# Headphone-Amplifier-ClassAB-alt4.net
KiCad netlist of a schematic drawn in EAGLE
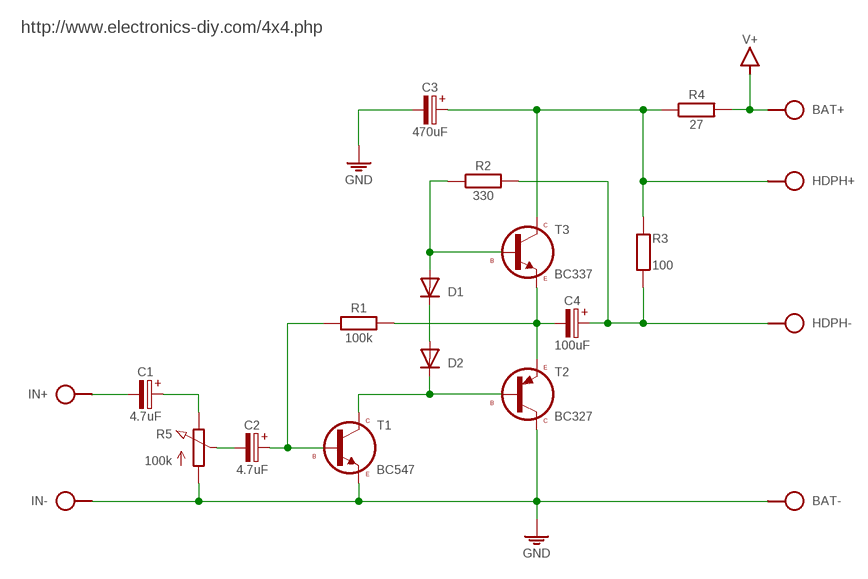
[diagram p0: schematic, sheet 1]

(export (version "E")
  (design (tool "Eeschema 10.0.6"))
  (components
    (comp (ref "BAT")
      (value "SPAD+-+-")
      (footprint "eagle-import:SPAD+-")
      (libsource (lib "eagle-import") (part "SPAD+-+-"))
    )
    (comp (ref "C1")
      (value "4.7uF")
      (footprint "eagle-import:E2,5-4")
      (libsource (lib "eagle-import") (part "CPOLE2,5-4"))
    )
    (comp (ref "C2")
      (value "4.7uF")
      (footprint "eagle-import:E2,5-4")
      (libsource (lib "eagle-import") (part "CPOLE2,5-4"))
    )
    (comp (ref "C3")
      (value "470uF")
      (footprint "eagle-import:E5-6")
      (libsource (lib "eagle-import") (part "CPOLE5-6"))
    )
    (comp (ref "C4")
      (value "100uF")
      (footprint "eagle-import:E5-4")
      (libsource (lib "eagle-import") (part "CPOLE5-4"))
    )
    (comp (ref "D1")
      (value "1N414834-5V")
      (footprint "eagle-import:DO34-5V")
      (libsource (lib "eagle-import") (part "1N414834-5V"))
    )
    (comp (ref "D2")
      (value "1N414834-5V")
      (footprint "eagle-import:DO34-5V")
      (libsource (lib "eagle-import") (part "1N414834-5V"))
    )
    (comp (ref "HDPH")
      (value "SPAD+--+")
      (footprint "eagle-import:SPAD-+")
      (libsource (lib "eagle-import") (part "SPAD+--+"))
    )
    (comp (ref "IN")
      (value "SPAD+--+")
      (footprint "eagle-import:SPAD-+")
      (libsource (lib "eagle-import") (part "SPAD+--+"))
    )
    (comp (ref "R1")
      (value "100k")
      (footprint "eagle-import:0202_7")
      (libsource (lib "eagle-import") (part "R-H0202/7"))
    )
    (comp (ref "R2")
      (value "330")
      (footprint "eagle-import:0202_7")
      (libsource (lib "eagle-import") (part "R-H0202/7"))
    )
    (comp (ref "R3")
      (value "100")
      (footprint "eagle-import:0202_7")
      (libsource (lib "eagle-import") (part "R0202/7"))
    )
    (comp (ref "R4")
      (value "27")
      (footprint "eagle-import:0204V")
      (libsource (lib "eagle-import") (part "R-H-V-X"))
    )
    (comp (ref "R5")
      (value "100k")
      (footprint "eagle-import:CONN-3P")
      (libsource (lib "eagle-import") (part "POT-3P"))
    )
    (comp (ref "T1")
      (value "BC547")
      (footprint "eagle-import:TO92")
      (libsource (lib "eagle-import") (part "BC547"))
    )
    (comp (ref "T2")
      (value "BC327")
      (footprint "eagle-import:TO92")
      (libsource (lib "eagle-import") (part "BC327"))
    )
    (comp (ref "T3")
      (value "BC337")
      (footprint "eagle-import:TO92-CBE")
      (libsource (lib "eagle-import") (part "BC337CBE"))
    )
  )
  (nets
    (net (code "1") (name "GND") (class "Default")
      (node (ref "BAT") (pin "1") (pinfunction "P$1_1") (pintype "passive"))
      (node (ref "C3") (pin "-") (pinfunction "-_-") (pintype "passive"))
      (node (ref "IN") (pin "1") (pinfunction "P$1_1") (pintype "passive"))
      (node (ref "R5") (pin "1") (pinfunction "A_1") (pintype "passive"))
      (node (ref "T1") (pin "3") (pinfunction "E_3") (pintype "passive"))
      (node (ref "T2") (pin "1") (pinfunction "C_1") (pintype "passive"))
    )
    (net (code "2") (name "Net-(D1-PadC)") (class "Default")
      (node (ref "D1") (pin "C") (pinfunction "C_C") (pintype "passive"))
      (node (ref "D2") (pin "A") (pinfunction "A_A") (pintype "passive"))
    )
    (net (code "3") (name "Net-(HDPHA-P$1)") (class "Default")
      (node (ref "C3") (pin "+") (pinfunction "+_+") (pintype "passive"))
      (node (ref "HDPH") (pin "2") (pinfunction "P$1_2") (pintype "passive"))
      (node (ref "R3") (pin "2") (pinfunction "1_2") (pintype "passive"))
      (node (ref "R4") (pin "2") (pinfunction "1_2") (pintype "passive"))
      (node (ref "T3") (pin "1") (pinfunction "C_1") (pintype "passive"))
    )
    (net (code "4") (name "Net-(HDPHB-P$1)") (class "Default")
      (node (ref "C4") (pin "+") (pinfunction "+_+") (pintype "passive"))
      (node (ref "HDPH") (pin "1") (pinfunction "P$1_1") (pintype "passive"))
      (node (ref "R2") (pin "2") (pinfunction "2_2") (pintype "passive"))
      (node (ref "R3") (pin "1") (pinfunction "2_1") (pintype "passive"))
    )
    (net (code "5") (name "Net-(INA-P$1)") (class "Default")
      (node (ref "C1") (pin "-") (pinfunction "-_-") (pintype "passive"))
      (node (ref "IN") (pin "2") (pinfunction "P$1_2") (pintype "passive"))
    )
    (net (code "6") (name "Net-(R5-E)") (class "Default")
      (node (ref "C1") (pin "+") (pinfunction "+_+") (pintype "passive"))
      (node (ref "R5") (pin "3") (pinfunction "E_3") (pintype "passive"))
    )
    (net (code "7") (name "Net-(R5-S)") (class "Default")
      (node (ref "C2") (pin "-") (pinfunction "-_-") (pintype "passive"))
      (node (ref "R5") (pin "2") (pinfunction "S_2") (pintype "passive"))
    )
    (net (code "8") (name "Net-(T1-B)") (class "Default")
      (node (ref "C2") (pin "+") (pinfunction "+_+") (pintype "passive"))
      (node (ref "R1") (pin "1") (pinfunction "1_1") (pintype "passive"))
      (node (ref "T1") (pin "2") (pinfunction "B_2") (pintype "passive"))
    )
    (net (code "9") (name "Net-(T1-C)") (class "Default")
      (node (ref "D2") (pin "C") (pinfunction "C_C") (pintype "passive"))
      (node (ref "T1") (pin "1") (pinfunction "C_1") (pintype "passive"))
      (node (ref "T2") (pin "2") (pinfunction "B_2") (pintype "passive"))
    )
    (net (code "10") (name "Net-(T2-E)") (class "Default")
      (node (ref "C4") (pin "-") (pinfunction "-_-") (pintype "passive"))
      (node (ref "R1") (pin "2") (pinfunction "2_2") (pintype "passive"))
      (node (ref "T2") (pin "3") (pinfunction "E_3") (pintype "passive"))
      (node (ref "T3") (pin "3") (pinfunction "E_3") (pintype "passive"))
    )
    (net (code "11") (name "Net-(T3-B)") (class "Default")
      (node (ref "D1") (pin "A") (pinfunction "A_A") (pintype "passive"))
      (node (ref "R2") (pin "1") (pinfunction "1_1") (pintype "passive"))
      (node (ref "T3") (pin "2") (pinfunction "B_2") (pintype "passive"))
    )
    (net (code "12") (name "V+") (class "Default")
      (node (ref "BAT") (pin "2") (pinfunction "P$1_2") (pintype "passive"))
      (node (ref "R4") (pin "1") (pinfunction "2_1") (pintype "passive"))
    )
  )
)
